# Mega_Design.net
KiCad netlist of a schematic drawn in EAGLE
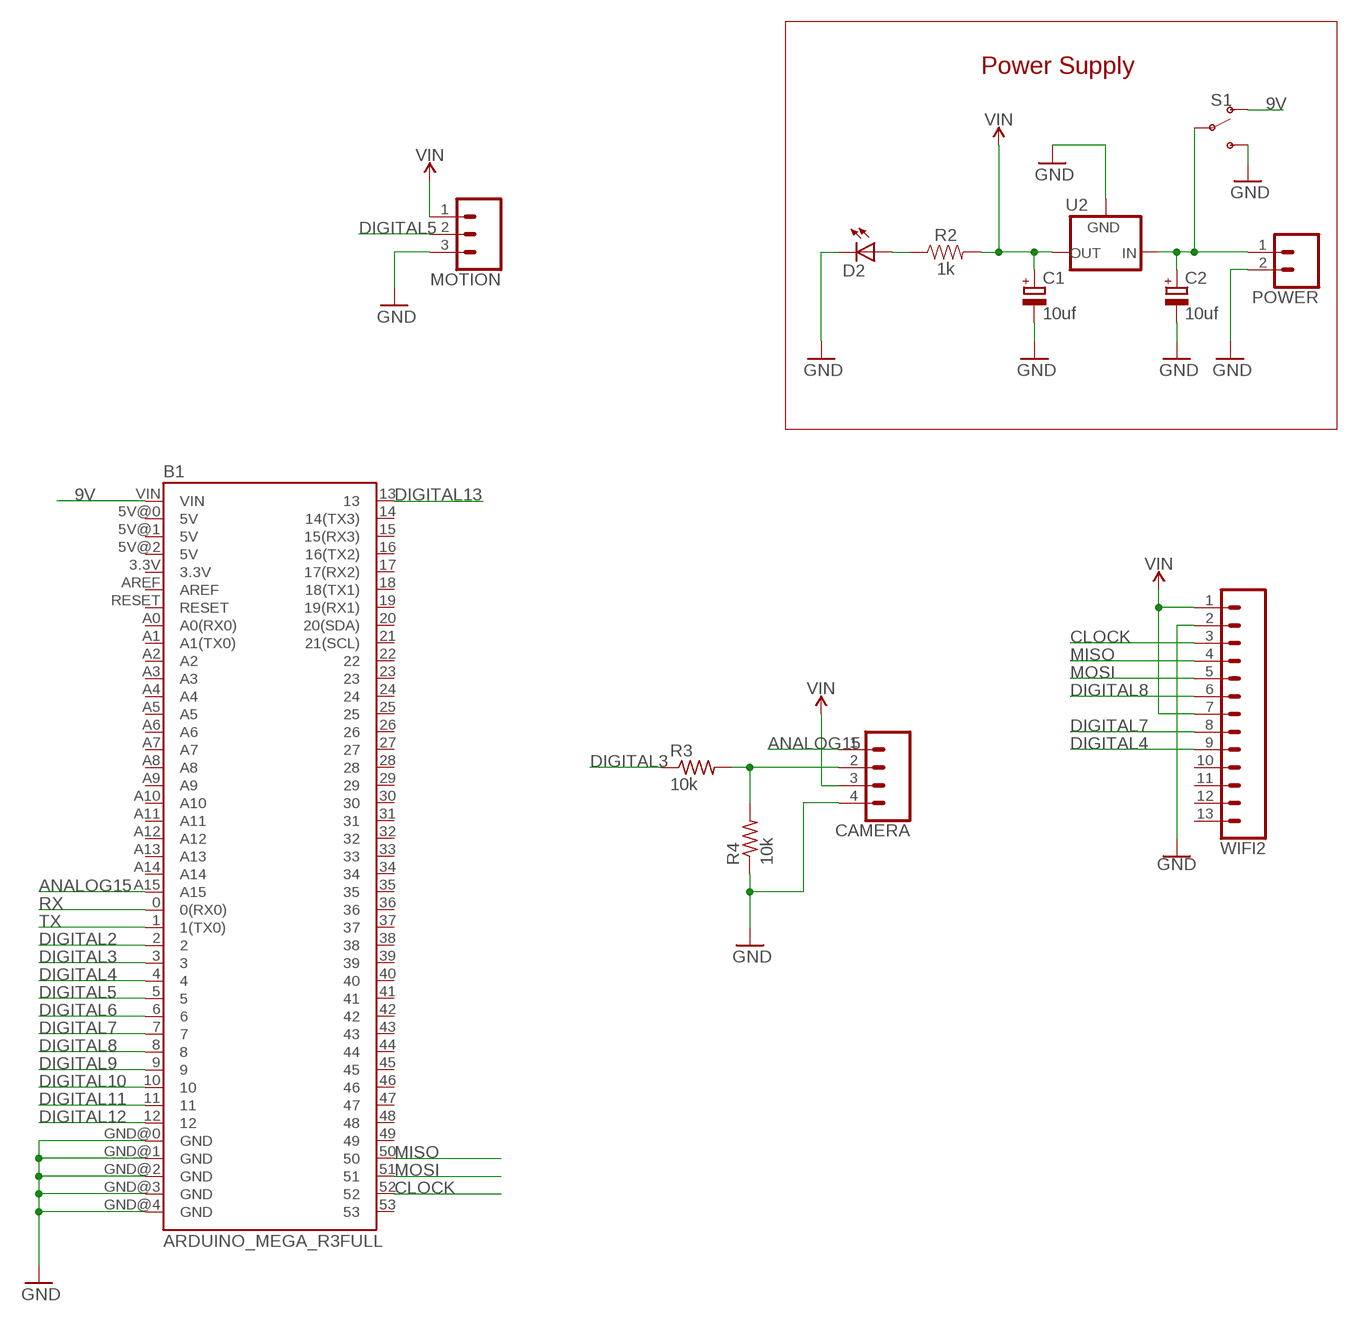
[diagram p0: schematic, sheet 1]

(export (version "E")
  (design (tool "Eeschema 10.0.6"))
  (components
    (comp (ref "B1")
      (value "ARDUINO_MEGA_R3FULL")
      (footprint "eagle-import:ARDUINO_MEGA")
      (libsource (lib "eagle-import") (part "ARDUINO_MEGA_R3FULL"))
    )
    (comp (ref "C1")
      (value "10uf")
      (footprint "eagle-import:E2,5-6")
      (libsource (lib "eagle-import") (part "CPOL-EUE2.5-6"))
    )
    (comp (ref "C2")
      (value "10uf")
      (footprint "eagle-import:E2,5-6")
      (libsource (lib "eagle-import") (part "CPOL-EUE2.5-6"))
    )
    (comp (ref "CAMERA")
      (value "CONN_04")
      (footprint "eagle-import:1X04")
      (libsource (lib "eagle-import") (part "CONN_04"))
    )
    (comp (ref "D2")
      (value "LED3MM")
      (footprint "eagle-import:LED3MM")
      (libsource (lib "eagle-import") (part "LED3MM"))
    )
    (comp (ref "MOTION")
      (value "CONN_03")
      (footprint "eagle-import:1X03")
      (libsource (lib "eagle-import") (part "CONN_03"))
    )
    (comp (ref "POWER")
      (value "CONN_025MM")
      (footprint "eagle-import:SCREWTERMINAL-5MM-2")
      (libsource (lib "eagle-import") (part "CONN_025MM"))
    )
    (comp (ref "R2")
      (value "1k")
      (footprint "eagle-import:AXIAL-0.3")
      (libsource (lib "eagle-import") (part "1KOHM-HORIZ-1/4W-5%"))
    )
    (comp (ref "R3")
      (value "10k")
      (footprint "eagle-import:0207_10")
      (libsource (lib "eagle-import") (part "R-US_0207/10"))
    )
    (comp (ref "R4")
      (value "10k")
      (footprint "eagle-import:0207_10")
      (libsource (lib "eagle-import") (part "R-US_0207/10"))
    )
    (comp (ref "S1")
      (value "SWITCH-SPDT-PTH-11.6X4.0MM")
      (footprint "eagle-import:SWITCH_SPDT_PTH_11.6X4.0MM")
      (libsource (lib "eagle-import") (part "SWITCH-SPDT-PTH-11.6X4.0MM"))
    )
    (comp (ref "U2")
      (value "V_REG_78XX-TO-220")
      (footprint "eagle-import:TO-220-ALT")
      (libsource (lib "eagle-import") (part "V_REG_78XX-TO-220"))
    )
    (comp (ref "WIFI2")
      (value "CONN_13")
      (footprint "eagle-import:1X13")
      (libsource (lib "eagle-import") (part "CONN_13"))
    )
  )
  (nets
    (net (code "1") (name "/9V") (class "Default")
      (node (ref "B1") (pin "VIN") (pinfunction "VIN_VIN") (pintype "bidirectional"))
      (node (ref "S1") (pin "1") (pinfunction "O_1") (pintype "passive"))
    )
    (net (code "2") (name "/ANALOG15") (class "Default")
      (node (ref "B1") (pin "A15") (pinfunction "A15_A15") (pintype "bidirectional"))
      (node (ref "CAMERA") (pin "1") (pinfunction "1_1") (pintype "passive"))
    )
    (net (code "3") (name "/CLOCK") (class "Default")
      (node (ref "B1") (pin "52") (pinfunction "52_52") (pintype "bidirectional"))
      (node (ref "WIFI2") (pin "3") (pinfunction "3_3") (pintype "passive"))
    )
    (net (code "4") (name "/DIGITAL2") (class "Default")
      (node (ref "B1") (pin "2") (pinfunction "2_2") (pintype "bidirectional"))
    )
    (net (code "5") (name "/DIGITAL3") (class "Default")
      (node (ref "B1") (pin "3") (pinfunction "3_3") (pintype "bidirectional"))
      (node (ref "R3") (pin "1") (pinfunction "1_1") (pintype "passive"))
    )
    (net (code "6") (name "/DIGITAL4") (class "Default")
      (node (ref "B1") (pin "4") (pinfunction "4_4") (pintype "bidirectional"))
      (node (ref "WIFI2") (pin "9") (pinfunction "9_9") (pintype "passive"))
    )
    (net (code "7") (name "/DIGITAL5") (class "Default")
      (node (ref "B1") (pin "5") (pinfunction "5_5") (pintype "bidirectional"))
      (node (ref "MOTION") (pin "2") (pinfunction "2_2") (pintype "passive"))
    )
    (net (code "8") (name "/DIGITAL6") (class "Default")
      (node (ref "B1") (pin "6") (pinfunction "6_6") (pintype "bidirectional"))
    )
    (net (code "9") (name "/DIGITAL7") (class "Default")
      (node (ref "B1") (pin "7") (pinfunction "7_7") (pintype "bidirectional"))
      (node (ref "WIFI2") (pin "8") (pinfunction "8_8") (pintype "passive"))
    )
    (net (code "10") (name "/DIGITAL8") (class "Default")
      (node (ref "B1") (pin "8") (pinfunction "8_8") (pintype "bidirectional"))
      (node (ref "WIFI2") (pin "6") (pinfunction "6_6") (pintype "passive"))
    )
    (net (code "11") (name "/DIGITAL9") (class "Default")
      (node (ref "B1") (pin "9") (pinfunction "9_9") (pintype "bidirectional"))
    )
    (net (code "12") (name "/DIGITAL10") (class "Default")
      (node (ref "B1") (pin "10") (pinfunction "10_10") (pintype "bidirectional"))
    )
    (net (code "13") (name "/DIGITAL11") (class "Default")
      (node (ref "B1") (pin "11") (pinfunction "11_11") (pintype "bidirectional"))
    )
    (net (code "14") (name "/DIGITAL12") (class "Default")
      (node (ref "B1") (pin "12") (pinfunction "12_12") (pintype "bidirectional"))
    )
    (net (code "15") (name "/DIGITAL13") (class "Default")
      (node (ref "B1") (pin "13") (pinfunction "13_13") (pintype "bidirectional"))
    )
    (net (code "16") (name "/MISO") (class "Default")
      (node (ref "B1") (pin "50") (pinfunction "50_50") (pintype "bidirectional"))
      (node (ref "WIFI2") (pin "4") (pinfunction "4_4") (pintype "passive"))
    )
    (net (code "17") (name "/MOSI") (class "Default")
      (node (ref "B1") (pin "51") (pinfunction "51_51") (pintype "bidirectional"))
      (node (ref "WIFI2") (pin "5") (pinfunction "5_5") (pintype "passive"))
    )
    (net (code "18") (name "/RX") (class "Default")
      (node (ref "B1") (pin "0") (pinfunction "0(RX0)_0") (pintype "bidirectional"))
    )
    (net (code "19") (name "/TX") (class "Default")
      (node (ref "B1") (pin "1") (pinfunction "1(TX0)_1") (pintype "bidirectional"))
    )
    (net (code "20") (name "GND") (class "Default")
      (node (ref "B1") (pin "GND@0") (pinfunction "GND_GND@0") (pintype "bidirectional"))
      (node (ref "B1") (pin "GND@1") (pinfunction "GND_GND@1") (pintype "bidirectional"))
      (node (ref "B1") (pin "GND@2") (pinfunction "GND_GND@2") (pintype "bidirectional"))
      (node (ref "B1") (pin "GND@3") (pinfunction "GND_GND@3") (pintype "bidirectional"))
      (node (ref "B1") (pin "GND@4") (pinfunction "GND_GND@4") (pintype "bidirectional"))
      (node (ref "C1") (pin "-") (pinfunction "-_-") (pintype "passive"))
      (node (ref "C2") (pin "-") (pinfunction "-_-") (pintype "passive"))
      (node (ref "CAMERA") (pin "4") (pinfunction "4_4") (pintype "passive"))
      (node (ref "D2") (pin "K") (pinfunction "C_K") (pintype "passive"))
      (node (ref "MOTION") (pin "3") (pinfunction "3_3") (pintype "passive"))
      (node (ref "POWER") (pin "2") (pinfunction "2_2") (pintype "passive"))
      (node (ref "R4") (pin "1") (pinfunction "1_1") (pintype "passive"))
      (node (ref "S1") (pin "3") (pinfunction "S_3") (pintype "passive"))
      (node (ref "U2") (pin "GND") (pinfunction "GND_GND") (pintype "input"))
      (node (ref "WIFI2") (pin "2") (pinfunction "2_2") (pintype "passive"))
    )
    (net (code "21") (name "Net-(CAMERA-Pad2)") (class "Default")
      (node (ref "CAMERA") (pin "2") (pinfunction "2_2") (pintype "passive"))
      (node (ref "R3") (pin "2") (pinfunction "2_2") (pintype "passive"))
      (node (ref "R4") (pin "2") (pinfunction "2_2") (pintype "passive"))
    )
    (net (code "22") (name "Net-(R2-1)") (class "Default")
      (node (ref "D2") (pin "A") (pinfunction "A_A") (pintype "passive"))
      (node (ref "R2") (pin "P$1") (pinfunction "1_P$1") (pintype "passive"))
    )
    (net (code "23") (name "Net-(S1-P)") (class "Default")
      (node (ref "C2") (pin "+") (pinfunction "+_+") (pintype "passive"))
      (node (ref "POWER") (pin "1") (pinfunction "1_1") (pintype "passive"))
      (node (ref "S1") (pin "2") (pinfunction "P_2") (pintype "passive"))
      (node (ref "U2") (pin "IN") (pinfunction "IN_IN") (pintype "input"))
    )
    (net (code "24") (name "VIN") (class "Default")
      (node (ref "C1") (pin "+") (pinfunction "+_+") (pintype "passive"))
      (node (ref "CAMERA") (pin "3") (pinfunction "3_3") (pintype "passive"))
      (node (ref "MOTION") (pin "1") (pinfunction "1_1") (pintype "passive"))
      (node (ref "R2") (pin "P$2") (pinfunction "2_P$2") (pintype "passive"))
      (node (ref "U2") (pin "OUT") (pinfunction "OUT_OUT") (pintype "passive"))
      (node (ref "WIFI2") (pin "1") (pinfunction "1_1") (pintype "passive"))
      (node (ref "WIFI2") (pin "7") (pinfunction "7_7") (pintype "passive"))
    )
    (net (code "25") (name "unconnected-(B1-5V-Pad5V@0)") (class "Default")
      (node (ref "B1") (pin "5V@0") (pinfunction "5V_5V@0") (pintype "bidirectional"))
    )
    (net (code "26") (name "unconnected-(B1-5V-Pad5V@1)") (class "Default")
      (node (ref "B1") (pin "5V@1") (pinfunction "5V_5V@1") (pintype "bidirectional"))
    )
    (net (code "27") (name "unconnected-(B1-5V-Pad5V@2)") (class "Default")
      (node (ref "B1") (pin "5V@2") (pinfunction "5V_5V@2") (pintype "bidirectional"))
    )
    (net (code "28") (name "unconnected-(B1-14(TX3)-Pad14)") (class "Default")
      (node (ref "B1") (pin "14") (pinfunction "14(TX3)_14") (pintype "bidirectional"))
    )
    (net (code "29") (name "unconnected-(B1-15(RX3)-Pad15)") (class "Default")
      (node (ref "B1") (pin "15") (pinfunction "15(RX3)_15") (pintype "bidirectional"))
    )
    (net (code "30") (name "unconnected-(B1-16(TX2)-Pad16)") (class "Default")
      (node (ref "B1") (pin "16") (pinfunction "16(TX2)_16") (pintype "bidirectional"))
    )
    (net (code "31") (name "unconnected-(B1-17(RX2)-Pad17)") (class "Default")
      (node (ref "B1") (pin "17") (pinfunction "17(RX2)_17") (pintype "bidirectional"))
    )
    (net (code "32") (name "unconnected-(B1-18(TX1)-Pad18)") (class "Default")
      (node (ref "B1") (pin "18") (pinfunction "18(TX1)_18") (pintype "bidirectional"))
    )
    (net (code "33") (name "unconnected-(B1-19(RX1)-Pad19)") (class "Default")
      (node (ref "B1") (pin "19") (pinfunction "19(RX1)_19") (pintype "bidirectional"))
    )
    (net (code "34") (name "unconnected-(B1-20(SDA)-Pad20)") (class "Default")
      (node (ref "B1") (pin "20") (pinfunction "20(SDA)_20") (pintype "bidirectional"))
    )
    (net (code "35") (name "unconnected-(B1-21(SCL)-Pad21)") (class "Default")
      (node (ref "B1") (pin "21") (pinfunction "21(SCL)_21") (pintype "bidirectional"))
    )
    (net (code "36") (name "unconnected-(B1-A0(RX0)-PadA0)") (class "Default")
      (node (ref "B1") (pin "A0") (pinfunction "A0(RX0)_A0") (pintype "bidirectional"))
    )
    (net (code "37") (name "unconnected-(B1-A1(TX0)-PadA1)") (class "Default")
      (node (ref "B1") (pin "A1") (pinfunction "A1(TX0)_A1") (pintype "bidirectional"))
    )
    (net (code "38") (name "unconnected-(B1-Pad3.3V)") (class "Default")
      (node (ref "B1") (pin "3.3V") (pinfunction "3.3V_3.3V") (pintype "bidirectional"))
    )
    (net (code "39") (name "unconnected-(B1-Pad22)") (class "Default")
      (node (ref "B1") (pin "22") (pinfunction "22_22") (pintype "bidirectional"))
    )
    (net (code "40") (name "unconnected-(B1-Pad23)") (class "Default")
      (node (ref "B1") (pin "23") (pinfunction "23_23") (pintype "bidirectional"))
    )
    (net (code "41") (name "unconnected-(B1-Pad24)") (class "Default")
      (node (ref "B1") (pin "24") (pinfunction "24_24") (pintype "bidirectional"))
    )
    (net (code "42") (name "unconnected-(B1-Pad25)") (class "Default")
      (node (ref "B1") (pin "25") (pinfunction "25_25") (pintype "bidirectional"))
    )
    (net (code "43") (name "unconnected-(B1-Pad26)") (class "Default")
      (node (ref "B1") (pin "26") (pinfunction "26_26") (pintype "bidirectional"))
    )
    (net (code "44") (name "unconnected-(B1-Pad27)") (class "Default")
      (node (ref "B1") (pin "27") (pinfunction "27_27") (pintype "bidirectional"))
    )
    (net (code "45") (name "unconnected-(B1-Pad28)") (class "Default")
      (node (ref "B1") (pin "28") (pinfunction "28_28") (pintype "bidirectional"))
    )
    (net (code "46") (name "unconnected-(B1-Pad29)") (class "Default")
      (node (ref "B1") (pin "29") (pinfunction "29_29") (pintype "bidirectional"))
    )
    (net (code "47") (name "unconnected-(B1-Pad30)") (class "Default")
      (node (ref "B1") (pin "30") (pinfunction "30_30") (pintype "bidirectional"))
    )
    (net (code "48") (name "unconnected-(B1-Pad31)") (class "Default")
      (node (ref "B1") (pin "31") (pinfunction "31_31") (pintype "bidirectional"))
    )
    (net (code "49") (name "unconnected-(B1-Pad32)") (class "Default")
      (node (ref "B1") (pin "32") (pinfunction "32_32") (pintype "bidirectional"))
    )
    (net (code "50") (name "unconnected-(B1-Pad33)") (class "Default")
      (node (ref "B1") (pin "33") (pinfunction "33_33") (pintype "bidirectional"))
    )
    (net (code "51") (name "unconnected-(B1-Pad34)") (class "Default")
      (node (ref "B1") (pin "34") (pinfunction "34_34") (pintype "bidirectional"))
    )
    (net (code "52") (name "unconnected-(B1-Pad35)") (class "Default")
      (node (ref "B1") (pin "35") (pinfunction "35_35") (pintype "bidirectional"))
    )
    (net (code "53") (name "unconnected-(B1-Pad36)") (class "Default")
      (node (ref "B1") (pin "36") (pinfunction "36_36") (pintype "bidirectional"))
    )
    (net (code "54") (name "unconnected-(B1-Pad37)") (class "Default")
      (node (ref "B1") (pin "37") (pinfunction "37_37") (pintype "bidirectional"))
    )
    (net (code "55") (name "unconnected-(B1-Pad38)") (class "Default")
      (node (ref "B1") (pin "38") (pinfunction "38_38") (pintype "bidirectional"))
    )
    (net (code "56") (name "unconnected-(B1-Pad39)") (class "Default")
      (node (ref "B1") (pin "39") (pinfunction "39_39") (pintype "bidirectional"))
    )
    (net (code "57") (name "unconnected-(B1-Pad40)") (class "Default")
      (node (ref "B1") (pin "40") (pinfunction "40_40") (pintype "bidirectional"))
    )
    (net (code "58") (name "unconnected-(B1-Pad41)") (class "Default")
      (node (ref "B1") (pin "41") (pinfunction "41_41") (pintype "bidirectional"))
    )
    (net (code "59") (name "unconnected-(B1-Pad42)") (class "Default")
      (node (ref "B1") (pin "42") (pinfunction "42_42") (pintype "bidirectional"))
    )
    (net (code "60") (name "unconnected-(B1-Pad43)") (class "Default")
      (node (ref "B1") (pin "43") (pinfunction "43_43") (pintype "bidirectional"))
    )
    (net (code "61") (name "unconnected-(B1-Pad44)") (class "Default")
      (node (ref "B1") (pin "44") (pinfunction "44_44") (pintype "bidirectional"))
    )
    (net (code "62") (name "unconnected-(B1-Pad45)") (class "Default")
      (node (ref "B1") (pin "45") (pinfunction "45_45") (pintype "bidirectional"))
    )
    (net (code "63") (name "unconnected-(B1-Pad46)") (class "Default")
      (node (ref "B1") (pin "46") (pinfunction "46_46") (pintype "bidirectional"))
    )
    (net (code "64") (name "unconnected-(B1-Pad47)") (class "Default")
      (node (ref "B1") (pin "47") (pinfunction "47_47") (pintype "bidirectional"))
    )
    (net (code "65") (name "unconnected-(B1-Pad48)") (class "Default")
      (node (ref "B1") (pin "48") (pinfunction "48_48") (pintype "bidirectional"))
    )
    (net (code "66") (name "unconnected-(B1-Pad49)") (class "Default")
      (node (ref "B1") (pin "49") (pinfunction "49_49") (pintype "bidirectional"))
    )
    (net (code "67") (name "unconnected-(B1-Pad53)") (class "Default")
      (node (ref "B1") (pin "53") (pinfunction "53_53") (pintype "bidirectional"))
    )
    (net (code "68") (name "unconnected-(B1-PadA2)") (class "Default")
      (node (ref "B1") (pin "A2") (pinfunction "A2_A2") (pintype "bidirectional"))
    )
    (net (code "69") (name "unconnected-(B1-PadA3)") (class "Default")
      (node (ref "B1") (pin "A3") (pinfunction "A3_A3") (pintype "bidirectional"))
    )
    (net (code "70") (name "unconnected-(B1-PadA4)") (class "Default")
      (node (ref "B1") (pin "A4") (pinfunction "A4_A4") (pintype "bidirectional"))
    )
    (net (code "71") (name "unconnected-(B1-PadA5)") (class "Default")
      (node (ref "B1") (pin "A5") (pinfunction "A5_A5") (pintype "bidirectional"))
    )
    (net (code "72") (name "unconnected-(B1-PadA6)") (class "Default")
      (node (ref "B1") (pin "A6") (pinfunction "A6_A6") (pintype "bidirectional"))
    )
    (net (code "73") (name "unconnected-(B1-PadA7)") (class "Default")
      (node (ref "B1") (pin "A7") (pinfunction "A7_A7") (pintype "bidirectional"))
    )
    (net (code "74") (name "unconnected-(B1-PadA8)") (class "Default")
      (node (ref "B1") (pin "A8") (pinfunction "A8_A8") (pintype "bidirectional"))
    )
    (net (code "75") (name "unconnected-(B1-PadA9)") (class "Default")
      (node (ref "B1") (pin "A9") (pinfunction "A9_A9") (pintype "bidirectional"))
    )
    (net (code "76") (name "unconnected-(B1-PadA10)") (class "Default")
      (node (ref "B1") (pin "A10") (pinfunction "A10_A10") (pintype "bidirectional"))
    )
    (net (code "77") (name "unconnected-(B1-PadA11)") (class "Default")
      (node (ref "B1") (pin "A11") (pinfunction "A11_A11") (pintype "bidirectional"))
    )
    (net (code "78") (name "unconnected-(B1-PadA12)") (class "Default")
      (node (ref "B1") (pin "A12") (pinfunction "A12_A12") (pintype "bidirectional"))
    )
    (net (code "79") (name "unconnected-(B1-PadA13)") (class "Default")
      (node (ref "B1") (pin "A13") (pinfunction "A13_A13") (pintype "bidirectional"))
    )
    (net (code "80") (name "unconnected-(B1-PadA14)") (class "Default")
      (node (ref "B1") (pin "A14") (pinfunction "A14_A14") (pintype "bidirectional"))
    )
    (net (code "81") (name "unconnected-(B1-PadAREF)") (class "Default")
      (node (ref "B1") (pin "AREF") (pinfunction "AREF_AREF") (pintype "bidirectional"))
    )
    (net (code "82") (name "unconnected-(B1-PadRESET)") (class "Default")
      (node (ref "B1") (pin "RESET") (pinfunction "RESET_RESET") (pintype "bidirectional"))
    )
    (net (code "83") (name "unconnected-(WIFI2-Pad10)") (class "Default")
      (node (ref "WIFI2") (pin "10") (pinfunction "10_10") (pintype "passive"))
    )
    (net (code "84") (name "unconnected-(WIFI2-Pad11)") (class "Default")
      (node (ref "WIFI2") (pin "11") (pinfunction "11_11") (pintype "passive"))
    )
    (net (code "85") (name "unconnected-(WIFI2-Pad12)") (class "Default")
      (node (ref "WIFI2") (pin "12") (pinfunction "12_12") (pintype "passive"))
    )
    (net (code "86") (name "unconnected-(WIFI2-Pad13)") (class "Default")
      (node (ref "WIFI2") (pin "13") (pinfunction "13_13") (pintype "passive"))
    )
  )
)
